# BeeLogic.net
KiCad netlist of a schematic drawn in EAGLE
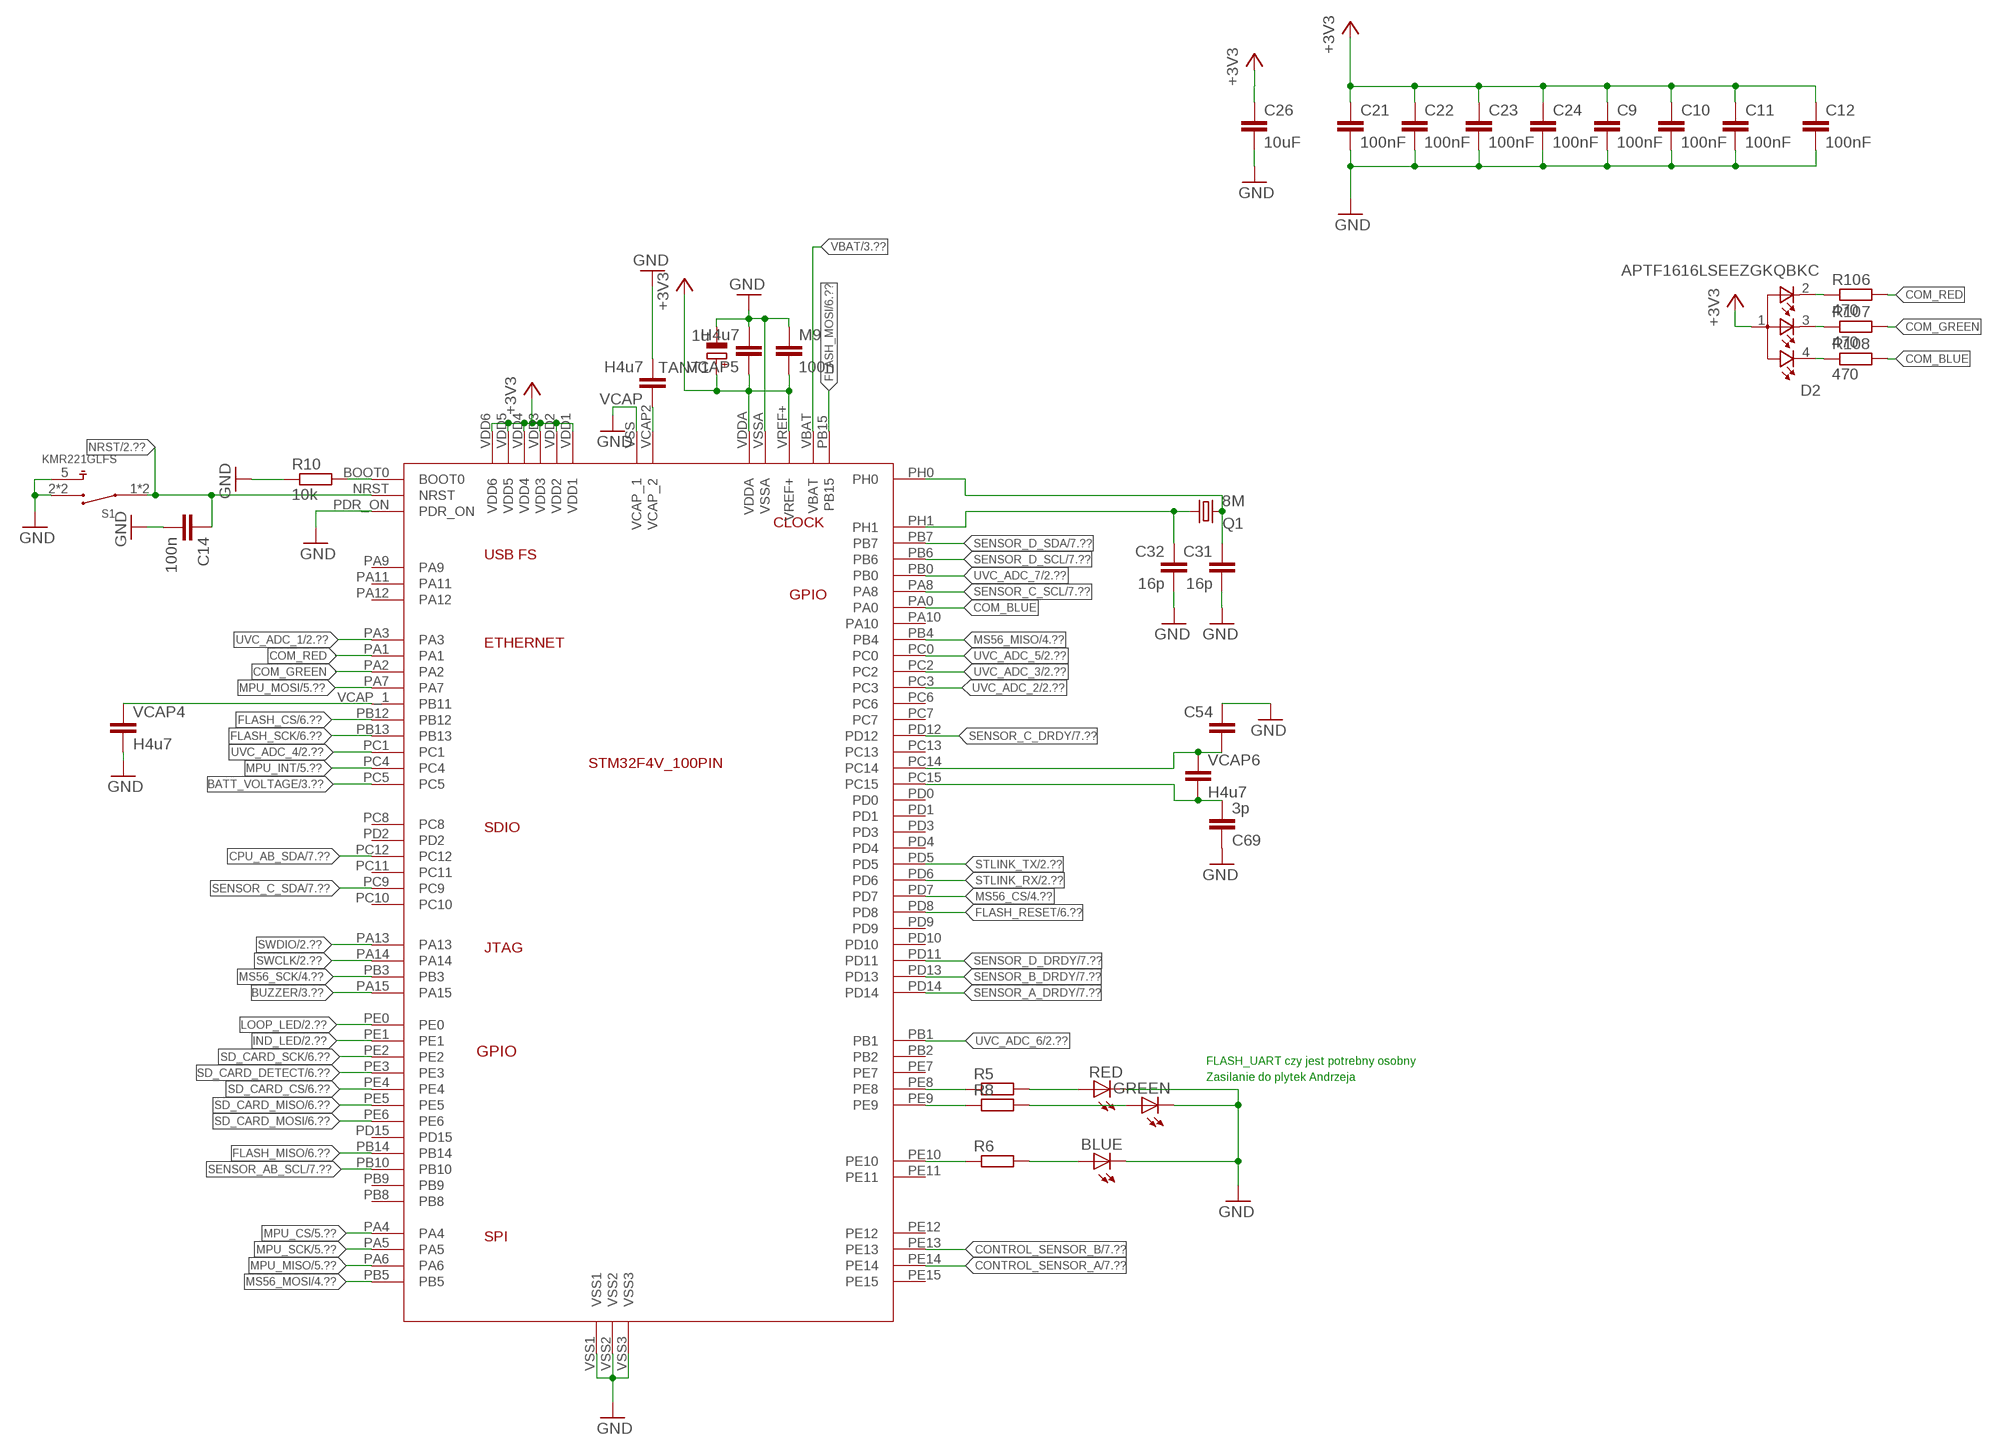
[diagram p0: schematic, sheet 1]
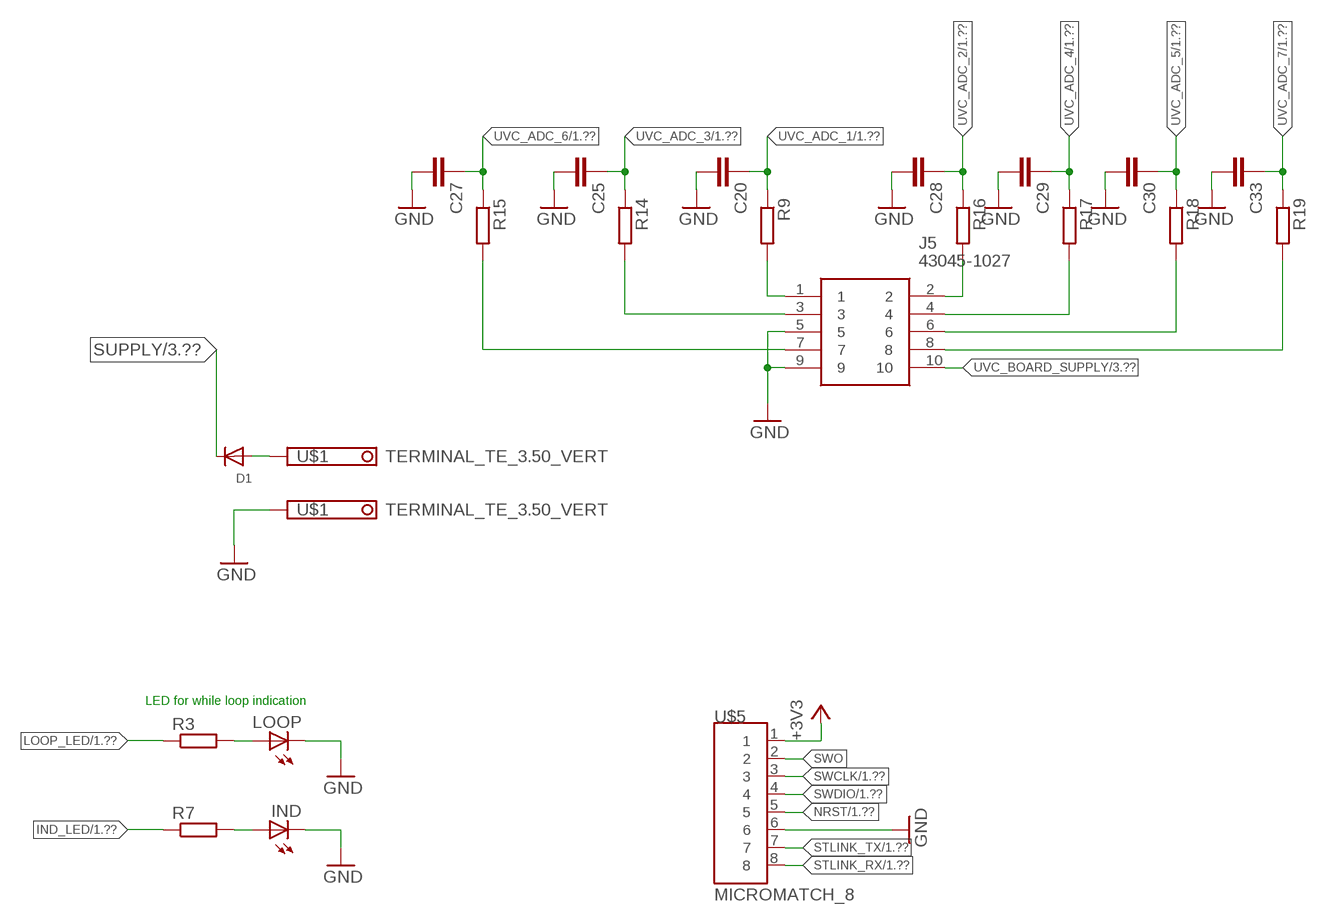
[diagram p1: schematic, sheet 2]
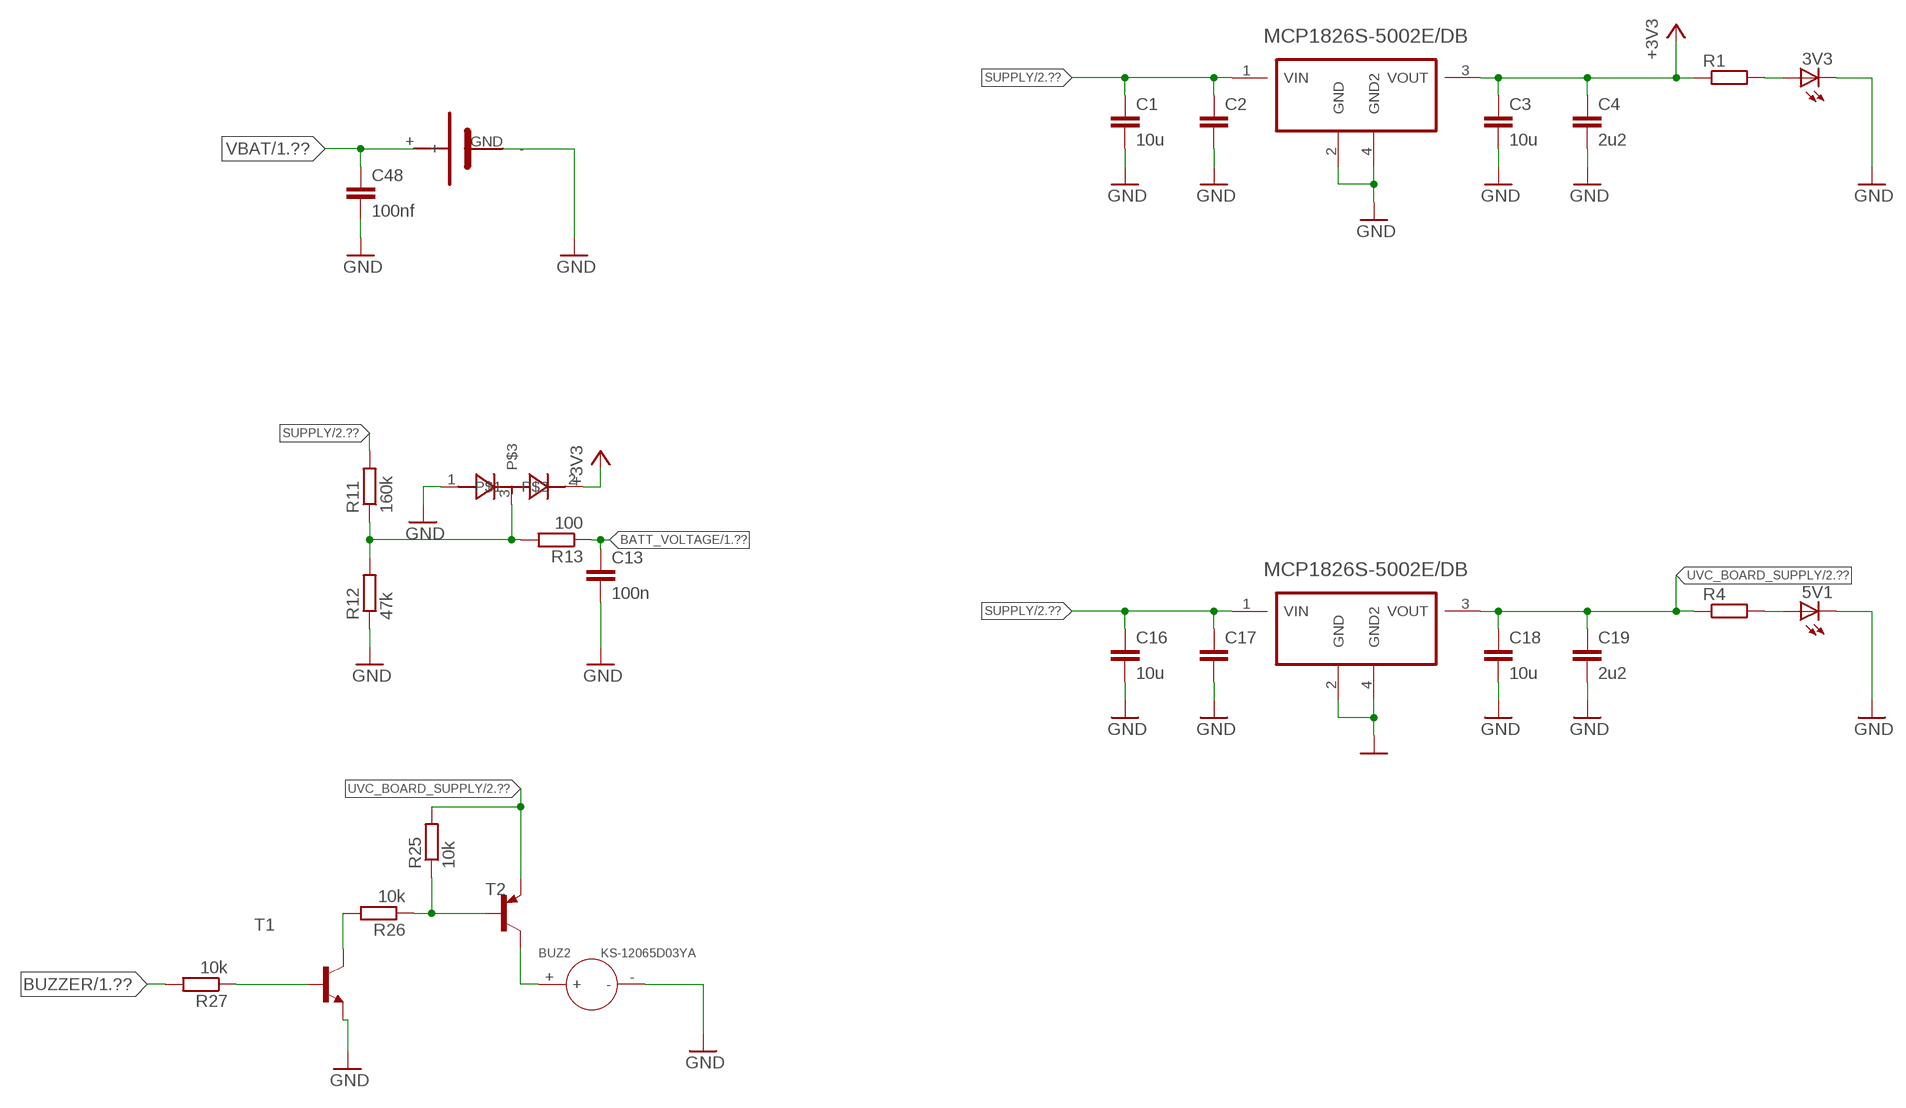
[diagram p2: schematic, sheet 3]
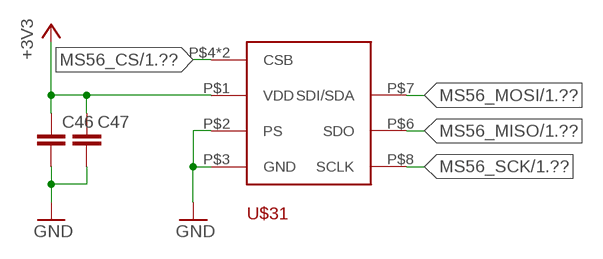
[diagram p3: schematic, sheet 4]
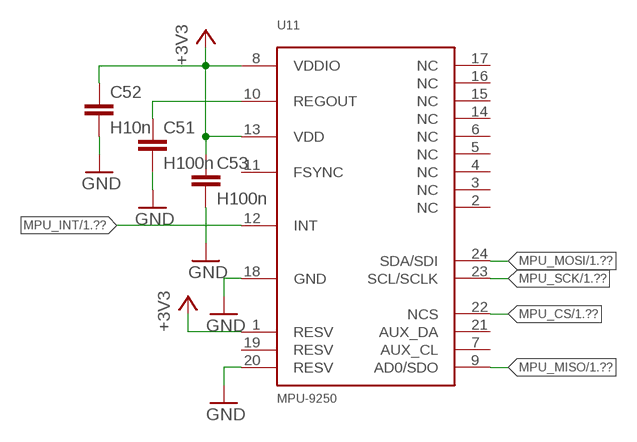
[diagram p4: schematic, sheet 5]
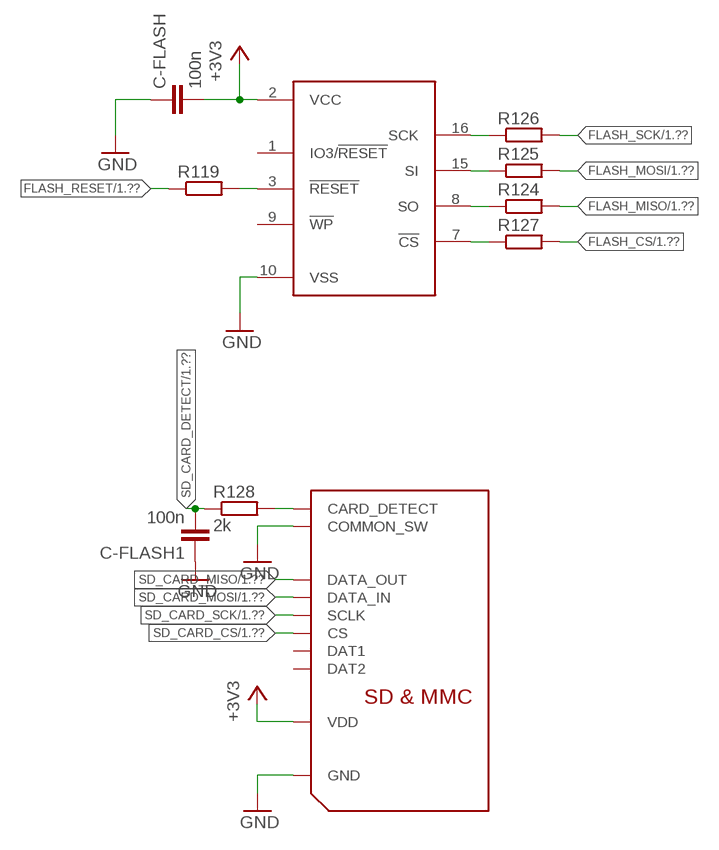
[diagram p5: schematic, sheet 6]
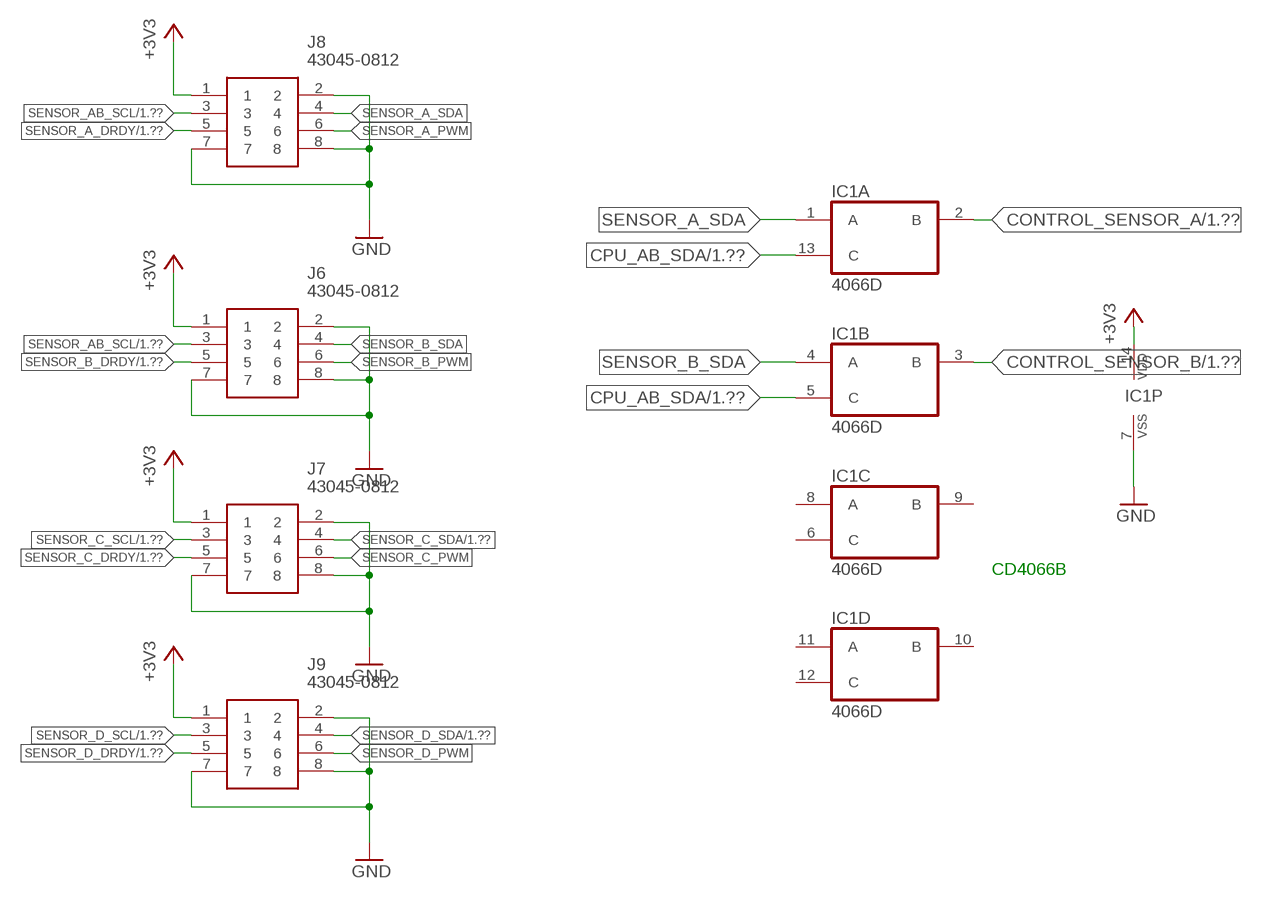
[diagram p6: schematic, sheet 7]

(export (version "E")
  (design (tool "Eeschema 10.0.6"))
  (components
    (comp (ref "IC1")
      (value "4066D")
      (footprint "eagle-import:SO14")
      (libsource (lib "eagle-import") (part "4066D"))
    )
    (comp (ref "J6")
      (value "43045-0812")
      (footprint "eagle-import:430450812")
      (fields (field (name "MOUSER_PART_NUMBER") "538-43045-0812"))
      (libsource (lib "eagle-import") (part "43045-0812"))
    )
    (comp (ref "J7")
      (value "43045-0812")
      (footprint "eagle-import:430450812")
      (fields (field (name "MOUSER_PART_NUMBER") "538-43045-0812"))
      (libsource (lib "eagle-import") (part "43045-0812"))
    )
    (comp (ref "J8")
      (value "43045-0812")
      (footprint "eagle-import:430450812")
      (fields (field (name "MOUSER_PART_NUMBER") "538-43045-0812"))
      (libsource (lib "eagle-import") (part "43045-0812"))
    )
    (comp (ref "J9")
      (value "43045-0812")
      (footprint "eagle-import:430450812")
      (fields (field (name "MOUSER_PART_NUMBER") "538-43045-0812"))
      (libsource (lib "eagle-import") (part "43045-0812"))
    )
    (comp (ref "BLUE")
      (value "LEDCHIPLED_0603")
      (footprint "eagle-import:CHIPLED_0603")
      (libsource (lib "eagle-import") (part "LEDCHIPLED_0603"))
    )
    (comp (ref "C9")
      (value "100nF")
      (footprint "eagle-import:C0603K")
      (libsource (lib "eagle-import") (part "rcl_334_C-EUC0603K"))
    )
    (comp (ref "C10")
      (value "100nF")
      (footprint "eagle-import:C0603K")
      (libsource (lib "eagle-import") (part "rcl_334_C-EUC0603K"))
    )
    (comp (ref "C11")
      (value "100nF")
      (footprint "eagle-import:C0603K")
      (libsource (lib "eagle-import") (part "rcl_334_C-EUC0603K"))
    )
    (comp (ref "C12")
      (value "100nF")
      (footprint "eagle-import:C0603K")
      (libsource (lib "eagle-import") (part "rcl_334_C-EUC0603K"))
    )
    (comp (ref "C14")
      (value "100n")
      (footprint "eagle-import:C0603K")
      (libsource (lib "eagle-import") (part "rcl_334_C-EUC0603K"))
    )
    (comp (ref "C21")
      (value "100nF")
      (footprint "eagle-import:C0603K")
      (libsource (lib "eagle-import") (part "rcl_334_C-EUC0603K"))
    )
    (comp (ref "C22")
      (value "100nF")
      (footprint "eagle-import:C0603K")
      (libsource (lib "eagle-import") (part "rcl_334_C-EUC0603K"))
    )
    (comp (ref "C23")
      (value "100nF")
      (footprint "eagle-import:C0603K")
      (libsource (lib "eagle-import") (part "rcl_334_C-EUC0603K"))
    )
    (comp (ref "C24")
      (value "100nF")
      (footprint "eagle-import:C0603K")
      (libsource (lib "eagle-import") (part "rcl_334_C-EUC0603K"))
    )
    (comp (ref "C26")
      (value "10uF")
      (footprint "eagle-import:C0805K")
      (libsource (lib "eagle-import") (part "rcl_334_C-EUC0805K"))
    )
    (comp (ref "C31")
      (value "16p")
      (footprint "eagle-import:C0603K")
      (libsource (lib "eagle-import") (part "rcl_334_C-EUC0603K"))
    )
    (comp (ref "C32")
      (value "16p")
      (footprint "eagle-import:C0603K")
      (libsource (lib "eagle-import") (part "rcl_334_C-EUC0603K"))
    )
    (comp (ref "C54")
      (value "3p")
      (footprint "eagle-import:C0603K")
      (libsource (lib "eagle-import") (part "rcl_334_C-EUC0603K"))
    )
    (comp (ref "C69")
      (value "3p")
      (footprint "eagle-import:C0603K")
      (libsource (lib "eagle-import") (part "rcl_334_C-EUC0603K"))
    )
    (comp (ref "D2")
      (value "APTF1616LSEEZGKQBKC")
      (footprint "eagle-import:LEDSC160X160X070-4N")
      (fields (field (name "MF") "Kingbright"))
      (libsource (lib "eagle-import") (part "APTF1616LSEEZGKQBKC"))
    )
    (comp (ref "GREEN")
      (value "LEDCHIPLED_0603")
      (footprint "eagle-import:CHIPLED_0603")
      (libsource (lib "eagle-import") (part "LEDCHIPLED_0603"))
    )
    (comp (ref "M9")
      (value "100n")
      (footprint "eagle-import:C0603K")
      (libsource (lib "eagle-import") (part "rcl_334_C-EUC0603K"))
    )
    (comp (ref "Q1")
      (value "8M")
      (footprint "eagle-import:CTS406")
      (libsource (lib "eagle-import") (part "CRYSTALCTS406"))
    )
    (comp (ref "R5")
      (value "R-EU_R0603")
      (footprint "eagle-import:R0603")
      (libsource (lib "eagle-import") (part "R-EU_R0603"))
    )
    (comp (ref "R6")
      (value "R-EU_R0603")
      (footprint "eagle-import:R0603")
      (libsource (lib "eagle-import") (part "R-EU_R0603"))
    )
    (comp (ref "R8")
      (value "R-EU_R0603")
      (footprint "eagle-import:R0603")
      (libsource (lib "eagle-import") (part "R-EU_R0603"))
    )
    (comp (ref "R10")
      (value "10k")
      (footprint "eagle-import:R0603")
      (libsource (lib "eagle-import") (part "R-EU_R0603"))
    )
    (comp (ref "R106")
      (value "470")
      (footprint "eagle-import:R0603")
      (libsource (lib "eagle-import") (part "R-EU_R0603"))
    )
    (comp (ref "R107")
      (value "470")
      (footprint "eagle-import:R0603")
      (libsource (lib "eagle-import") (part "R-EU_R0603"))
    )
    (comp (ref "R108")
      (value "470")
      (footprint "eagle-import:R0603")
      (libsource (lib "eagle-import") (part "R-EU_R0603"))
    )
    (comp (ref "RED")
      (value "LEDCHIPLED_0603")
      (footprint "eagle-import:CHIPLED_0603")
      (libsource (lib "eagle-import") (part "LEDCHIPLED_0603"))
    )
    (comp (ref "S1")
      (value "KMR221GLFS")
      (footprint "eagle-import:SW_KMR221GLFS")
      (fields (field (name "MF") "C&K Components"))
      (libsource (lib "eagle-import") (part "KMR221GLFS"))
    )
    (comp (ref "STM32F446VET1")
      (value "STM32F4V_100PIN_GPSBOARD")
      (footprint "eagle-import:LQFP100")
      (libsource (lib "eagle-import") (part "STM32F4V_100PIN_GPSBOARD"))
    )
    (comp (ref "TANT1")
      (value "1u")
      (footprint "eagle-import:SMC_A")
      (libsource (lib "eagle-import") (part "CPOL-EUSMCA"))
    )
    (comp (ref "VCAP")
      (value "H4u7")
      (footprint "eagle-import:C0805K")
      (libsource (lib "eagle-import") (part "rcl_334_C-EUC0805K"))
    )
    (comp (ref "VCAP4")
      (value "H4u7")
      (footprint "eagle-import:C0805K")
      (libsource (lib "eagle-import") (part "rcl_334_C-EUC0805K"))
    )
    (comp (ref "VCAP5")
      (value "H4u7")
      (footprint "eagle-import:C0805K")
      (libsource (lib "eagle-import") (part "rcl_334_C-EUC0805K"))
    )
    (comp (ref "VCAP6")
      (value "H4u7")
      (footprint "eagle-import:C0805K")
      (libsource (lib "eagle-import") (part "rcl_334_C-EUC0805K"))
    )
    (comp (ref "C46")
      (value "C-EUC0603")
      (footprint "eagle-import:C0603")
      (libsource (lib "eagle-import") (part "rcl_334_C-EUC0603"))
    )
    (comp (ref "C47")
      (value "C-EUC0603")
      (footprint "eagle-import:C0603")
      (libsource (lib "eagle-import") (part "rcl_334_C-EUC0603"))
    )
    (comp (ref "U$31")
      (value "MS56XX")
      (footprint "eagle-import:MS56XX")
      (libsource (lib "eagle-import") (part "MS56XX"))
    )
    (comp (ref "C-FLASH")
      (value "100n")
      (footprint "eagle-import:C0603K")
      (libsource (lib "eagle-import") (part "rcl_334_C-EUC0603K"))
    )
    (comp (ref "C-FLASH1")
      (value "100n")
      (footprint "eagle-import:C0603K")
      (libsource (lib "eagle-import") (part "rcl_334_C-EUC0603K"))
    )
    (comp (ref "R119")
      (value "R-EU_R0603")
      (footprint "eagle-import:R0603")
      (libsource (lib "eagle-import") (part "R-EU_R0603"))
    )
    (comp (ref "R124")
      (value "R-EU_R0603")
      (footprint "eagle-import:R0603")
      (libsource (lib "eagle-import") (part "R-EU_R0603"))
    )
    (comp (ref "R125")
      (value "R-EU_R0603")
      (footprint "eagle-import:R0603")
      (libsource (lib "eagle-import") (part "R-EU_R0603"))
    )
    (comp (ref "R126")
      (value "R-EU_R0603")
      (footprint "eagle-import:R0603")
      (libsource (lib "eagle-import") (part "R-EU_R0603"))
    )
    (comp (ref "R127")
      (value "R-EU_R0603")
      (footprint "eagle-import:R0603")
      (libsource (lib "eagle-import") (part "R-EU_R0603"))
    )
    (comp (ref "R128")
      (value "2k")
      (footprint "eagle-import:R0603")
      (libsource (lib "eagle-import") (part "R-EU_R0603"))
    )
    (comp (ref "U$2")
      (value "S25FLX")
      (footprint "eagle-import:SOIC16")
      (libsource (lib "eagle-import") (part "S25FLX"))
    )
    (comp (ref "U$4")
      (value "MOLEX_MICRO_SD_503182-1853")
      (footprint "eagle-import:MOLEX_MICRO_SD_503182-1853")
      (fields (field (name "SPICEPREFIX") "X"))
      (libsource (lib "eagle-import") (part "MOLEX_MICRO_SD_503182-1853"))
    )
    (comp (ref "3V3")
      (value "LEDCHIPLED_0603")
      (footprint "eagle-import:CHIPLED_0603")
      (libsource (lib "eagle-import") (part "LEDCHIPLED_0603"))
    )
    (comp (ref "5V1")
      (value "LEDCHIPLED_0603")
      (footprint "eagle-import:CHIPLED_0603")
      (libsource (lib "eagle-import") (part "LEDCHIPLED_0603"))
    )
    (comp (ref "BUZ2")
      (value "KS-12065D03YA")
      (footprint "eagle-import:BZ2-7.6-D12.0XH6.5MM")
      (libsource (lib "eagle-import") (part "DIP-BUZZER-3V(KS-12065D03YA)"))
    )
    (comp (ref "C1")
      (value "10u")
      (footprint "eagle-import:C0805K")
      (libsource (lib "eagle-import") (part "rcl_334_C-EUC0805K"))
    )
    (comp (ref "C2")
      (value "C-EUC0805K")
      (footprint "eagle-import:C0805K")
      (libsource (lib "eagle-import") (part "rcl_334_C-EUC0805K"))
    )
    (comp (ref "C3")
      (value "10u")
      (footprint "eagle-import:C0805K")
      (libsource (lib "eagle-import") (part "rcl_334_C-EUC0805K"))
    )
    (comp (ref "C4")
      (value "2u2")
      (footprint "eagle-import:C0805K")
      (libsource (lib "eagle-import") (part "rcl_334_C-EUC0805K"))
    )
    (comp (ref "C13")
      (value "100n")
      (footprint "eagle-import:C0603")
      (libsource (lib "eagle-import") (part "C-EUC0603"))
    )
    (comp (ref "C16")
      (value "10u")
      (footprint "eagle-import:C0805K")
      (libsource (lib "eagle-import") (part "rcl_334_C-EUC0805K"))
    )
    (comp (ref "C17")
      (value "C-EUC0805K")
      (footprint "eagle-import:C0805K")
      (libsource (lib "eagle-import") (part "rcl_334_C-EUC0805K"))
    )
    (comp (ref "C18")
      (value "10u")
      (footprint "eagle-import:C0805K")
      (libsource (lib "eagle-import") (part "rcl_334_C-EUC0805K"))
    )
    (comp (ref "C19")
      (value "2u2")
      (footprint "eagle-import:C0805K")
      (libsource (lib "eagle-import") (part "rcl_334_C-EUC0805K"))
    )
    (comp (ref "C48")
      (value "100nf")
      (footprint "eagle-import:C0805K")
      (libsource (lib "eagle-import") (part "rcl_334_C-EUC0805K"))
    )
    (comp (ref "R1")
      (value "R-EU_R0603")
      (footprint "eagle-import:R0603")
      (libsource (lib "eagle-import") (part "R-EU_R0603"))
    )
    (comp (ref "R4")
      (value "R-EU_R0603")
      (footprint "eagle-import:R0603")
      (libsource (lib "eagle-import") (part "R-EU_R0603"))
    )
    (comp (ref "R11")
      (value "160k")
      (footprint "eagle-import:R0603")
      (libsource (lib "eagle-import") (part "R-EU_R0603"))
    )
    (comp (ref "R12")
      (value "47k")
      (footprint "eagle-import:R0603")
      (libsource (lib "eagle-import") (part "R-EU_R0603"))
    )
    (comp (ref "R13")
      (value "100")
      (footprint "eagle-import:R0603")
      (libsource (lib "eagle-import") (part "R-EU_R0603"))
    )
    (comp (ref "R25")
      (value "10k")
      (footprint "eagle-import:R0603")
      (libsource (lib "eagle-import") (part "R-EU_R0603"))
    )
    (comp (ref "R26")
      (value "10k")
      (footprint "eagle-import:R0603")
      (libsource (lib "eagle-import") (part "R-EU_R0603"))
    )
    (comp (ref "R27")
      (value "10k")
      (footprint "eagle-import:R0603")
      (libsource (lib "eagle-import") (part "R-EU_R0603"))
    )
    (comp (ref "T1")
      (value "BCW81-NPN-SOT23-BEC")
      (footprint "eagle-import:SOT23-BEC")
      (libsource (lib "eagle-import") (part "-NPN-SOT23-BECBCW81"))
    )
    (comp (ref "T2")
      (value "BC807-16-PNP-SOT23-BEC")
      (footprint "eagle-import:SOT23-BEC")
      (libsource (lib "eagle-import") (part "-PNP-SOT23-BECBC807-16"))
    )
    (comp (ref "U$16")
      (value "BAS40W-04")
      (footprint "eagle-import:SOT65P210X110-3N")
      (libsource (lib "eagle-import") (part "BAS40W-04"))
    )
    (comp (ref "U$32")
      (value "CR1220_POZ")
      (footprint "eagle-import:CR1220_POZ")
      (libsource (lib "eagle-import") (part "CR1220_POZ"))
    )
    (comp (ref "U1")
      (value "MCP1826S-5002E/DB")
      (footprint "eagle-import:SOT230P700X180-4N")
      (fields (field (name "MF") "Microchip"))
      (libsource (lib "eagle-import") (part "MCP1826S-5002E/DB"))
    )
    (comp (ref "U3")
      (value "MCP1826S-5002E/DB")
      (footprint "eagle-import:SOT230P700X180-4N")
      (fields (field (name "MF") "Microchip"))
      (libsource (lib "eagle-import") (part "MCP1826S-5002E/DB"))
    )
    (comp (ref "C20")
      (value "C-EUC0603")
      (footprint "eagle-import:C0603")
      (libsource (lib "eagle-import") (part "resistor_348_C-EUC0603"))
    )
    (comp (ref "C25")
      (value "C-EUC0603")
      (footprint "eagle-import:C0603")
      (libsource (lib "eagle-import") (part "resistor_348_C-EUC0603"))
    )
    (comp (ref "C27")
      (value "C-EUC0603")
      (footprint "eagle-import:C0603")
      (libsource (lib "eagle-import") (part "resistor_348_C-EUC0603"))
    )
    (comp (ref "C28")
      (value "C-EUC0603")
      (footprint "eagle-import:C0603")
      (libsource (lib "eagle-import") (part "resistor_348_C-EUC0603"))
    )
    (comp (ref "C29")
      (value "C-EUC0603")
      (footprint "eagle-import:C0603")
      (libsource (lib "eagle-import") (part "resistor_348_C-EUC0603"))
    )
    (comp (ref "C30")
      (value "C-EUC0603")
      (footprint "eagle-import:C0603")
      (libsource (lib "eagle-import") (part "resistor_348_C-EUC0603"))
    )
    (comp (ref "C33")
      (value "C-EUC0603")
      (footprint "eagle-import:C0603")
      (libsource (lib "eagle-import") (part "resistor_348_C-EUC0603"))
    )
    (comp (ref "D1")
      (value "DIODE_SOD-123FL")
      (footprint "eagle-import:SOD-123FL")
      (libsource (lib "eagle-import") (part "DIODE_SOD-123FL"))
    )
    (comp (ref "IND")
      (value "LEDCHIPLED_0603")
      (footprint "eagle-import:CHIPLED_0603")
      (libsource (lib "eagle-import") (part "LEDCHIPLED_0603"))
    )
    (comp (ref "J5")
      (value "43045-1027")
      (footprint "eagle-import:43045-1028_1")
      (fields (field (name "MOUSER_PART_NUMBER") "538-43045-1027") (field (name "RS_PART_NUMBER") "6700469P"))
      (libsource (lib "eagle-import") (part "43045-1027"))
    )
    (comp (ref "LOOP")
      (value "LEDCHIPLED_0603")
      (footprint "eagle-import:CHIPLED_0603")
      (libsource (lib "eagle-import") (part "LEDCHIPLED_0603"))
    )
    (comp (ref "R3")
      (value "R-EU_R0603")
      (footprint "eagle-import:R0603")
      (libsource (lib "eagle-import") (part "R-EU_R0603"))
    )
    (comp (ref "R7")
      (value "R-EU_R0603")
      (footprint "eagle-import:R0603")
      (libsource (lib "eagle-import") (part "R-EU_R0603"))
    )
    (comp (ref "R9")
      (value "R-EU_R0603")
      (footprint "eagle-import:R0603")
      (libsource (lib "eagle-import") (part "resistor_348_R-EU_R0603"))
    )
    (comp (ref "R14")
      (value "R-EU_R0603")
      (footprint "eagle-import:R0603")
      (libsource (lib "eagle-import") (part "resistor_348_R-EU_R0603"))
    )
    (comp (ref "R15")
      (value "R-EU_R0603")
      (footprint "eagle-import:R0603")
      (libsource (lib "eagle-import") (part "resistor_348_R-EU_R0603"))
    )
    (comp (ref "R16")
      (value "R-EU_R0603")
      (footprint "eagle-import:R0603")
      (libsource (lib "eagle-import") (part "resistor_348_R-EU_R0603"))
    )
    (comp (ref "R17")
      (value "R-EU_R0603")
      (footprint "eagle-import:R0603")
      (libsource (lib "eagle-import") (part "resistor_348_R-EU_R0603"))
    )
    (comp (ref "R18")
      (value "R-EU_R0603")
      (footprint "eagle-import:R0603")
      (libsource (lib "eagle-import") (part "resistor_348_R-EU_R0603"))
    )
    (comp (ref "R19")
      (value "R-EU_R0603")
      (footprint "eagle-import:R0603")
      (libsource (lib "eagle-import") (part "resistor_348_R-EU_R0603"))
    )
    (comp (ref "U$1")
      (value "TERMINAL_TE_3.50_VERT")
      (footprint "eagle-import:TE_3.5_TERMINAL_VERT")
      (libsource (lib "eagle-import") (part "TERMINAL_TE_3.50_VERT"))
    )
    (comp (ref "U$5")
      (value "MICROMATCH_8")
      (footprint "eagle-import:MICROMATCH_8")
      (libsource (lib "eagle-import") (part "MICROMATCH_8"))
    )
    (comp (ref "C51")
      (value "H100n")
      (footprint "eagle-import:C0603K")
      (libsource (lib "eagle-import") (part "rcl_334_C-EUC0603K"))
    )
    (comp (ref "C52")
      (value "H10n")
      (footprint "eagle-import:C0603K")
      (libsource (lib "eagle-import") (part "rcl_334_C-EUC0603K"))
    )
    (comp (ref "C53")
      (value "H100n")
      (footprint "eagle-import:C0603K")
      (libsource (lib "eagle-import") (part "rcl_334_C-EUC0603K"))
    )
    (comp (ref "U11")
      (value "MPU-9250")
      (footprint "eagle-import:MPU-9250")
      (fields (field (name "MF") "InvenSense"))
      (libsource (lib "eagle-import") (part "MPU-9250"))
    )
  )
  (nets
    (net (code "1") (name "+3V3") (class "Default")
      (node (ref "C-FLASH") (pin "2") (pinfunction "2_2") (pintype "passive"))
      (node (ref "C10") (pin "1") (pinfunction "1_1") (pintype "passive"))
      (node (ref "C11") (pin "1") (pinfunction "1_1") (pintype "passive"))
      (node (ref "C12") (pin "1") (pinfunction "1_1") (pintype "passive"))
      (node (ref "C21") (pin "1") (pinfunction "1_1") (pintype "passive"))
      (node (ref "C22") (pin "1") (pinfunction "1_1") (pintype "passive"))
      (node (ref "C23") (pin "1") (pinfunction "1_1") (pintype "passive"))
      (node (ref "C24") (pin "1") (pinfunction "1_1") (pintype "passive"))
      (node (ref "C26") (pin "1") (pinfunction "1_1") (pintype "passive"))
      (node (ref "C3") (pin "1") (pinfunction "1_1") (pintype "passive"))
      (node (ref "C4") (pin "1") (pinfunction "1_1") (pintype "passive"))
      (node (ref "C46") (pin "1") (pinfunction "1_1") (pintype "passive"))
      (node (ref "C47") (pin "1") (pinfunction "1_1") (pintype "passive"))
      (node (ref "C52") (pin "1") (pinfunction "1_1") (pintype "passive"))
      (node (ref "C53") (pin "1") (pinfunction "1_1") (pintype "passive"))
      (node (ref "C9") (pin "1") (pinfunction "1_1") (pintype "passive"))
      (node (ref "D2") (pin "1") (pinfunction "1_1") (pintype "passive"))
      (node (ref "IC1") (pin "14") (pinfunction "VDD_14") (pintype "power_in"))
      (node (ref "J6") (pin "1") (pinfunction "1_1") (pintype "bidirectional"))
      (node (ref "J7") (pin "1") (pinfunction "1_1") (pintype "bidirectional"))
      (node (ref "J8") (pin "1") (pinfunction "1_1") (pintype "bidirectional"))
      (node (ref "J9") (pin "1") (pinfunction "1_1") (pintype "bidirectional"))
      (node (ref "M9") (pin "2") (pinfunction "2_2") (pintype "passive"))
      (node (ref "R1") (pin "1") (pinfunction "1_1") (pintype "passive"))
      (node (ref "STM32F446VET1") (pin "VDD1") (pinfunction "VDD1_VDD1") (pintype "power_in"))
      (node (ref "STM32F446VET1") (pin "VDD2") (pinfunction "VDD2_VDD2") (pintype "power_in"))
      (node (ref "STM32F446VET1") (pin "VDD3") (pinfunction "VDD3_VDD3") (pintype "power_in"))
      (node (ref "STM32F446VET1") (pin "VDD4") (pinfunction "VDD4_VDD4") (pintype "power_in"))
      (node (ref "STM32F446VET1") (pin "VDD5") (pinfunction "VDD5_VDD5") (pintype "power_in"))
      (node (ref "STM32F446VET1") (pin "VDD6") (pinfunction "VDD6_VDD6") (pintype "power_in"))
      (node (ref "STM32F446VET1") (pin "VDDA") (pinfunction "VDDA_VDDA") (pintype "bidirectional"))
      (node (ref "STM32F446VET1") (pin "VREF+") (pinfunction "VREF+_VREF+") (pintype "bidirectional"))
      (node (ref "TANT1") (pin "+") (pinfunction "+_+") (pintype "passive"))
      (node (ref "U$16") (pin "2") (pinfunction "P$2_2") (pintype "bidirectional"))
      (node (ref "U$2") (pin "2") (pinfunction "VCC_2") (pintype "bidirectional"))
      (node (ref "U$31") (pin "P$1") (pinfunction "VDD_P$1") (pintype "bidirectional"))
      (node (ref "U$4") (pin "PIN4") (pinfunction "VDD_PIN4") (pintype "power_in"))
      (node (ref "U$5") (pin "1") (pinfunction "1_1") (pintype "passive"))
      (node (ref "U1") (pin "3") (pinfunction "VOUT_3") (pintype "output"))
      (node (ref "U11") (pin "1") (pinfunction "RESV_1") (pintype "bidirectional"))
      (node (ref "U11") (pin "13") (pinfunction "VDD_13") (pintype "bidirectional"))
      (node (ref "U11") (pin "8") (pinfunction "VDDIO_8") (pintype "bidirectional"))
      (node (ref "VCAP5") (pin "1") (pinfunction "1_1") (pintype "passive"))
    )
    (net (code "2") (name "BATT_VOLTAGE") (class "Default")
      (node (ref "C13") (pin "1") (pinfunction "1_1") (pintype "passive"))
      (node (ref "R13") (pin "1") (pinfunction "1_1") (pintype "passive"))
      (node (ref "STM32F446VET1") (pin "PC5") (pinfunction "PC5_PC5") (pintype "bidirectional"))
    )
    (net (code "3") (name "BUZZER") (class "Default")
      (node (ref "R27") (pin "2") (pinfunction "2_2") (pintype "passive"))
      (node (ref "STM32F446VET1") (pin "PA15") (pinfunction "PA15_PA15") (pintype "bidirectional"))
    )
    (net (code "4") (name "COM_BLUE") (class "Default")
      (node (ref "R108") (pin "2") (pinfunction "2_2") (pintype "passive"))
      (node (ref "STM32F446VET1") (pin "PA0") (pinfunction "PA0_PA0") (pintype "bidirectional"))
    )
    (net (code "5") (name "COM_GREEN") (class "Default")
      (node (ref "R107") (pin "2") (pinfunction "2_2") (pintype "passive"))
      (node (ref "STM32F446VET1") (pin "PA2") (pinfunction "PA2_PA2") (pintype "bidirectional"))
    )
    (net (code "6") (name "COM_RED") (class "Default")
      (node (ref "R106") (pin "2") (pinfunction "2_2") (pintype "passive"))
      (node (ref "STM32F446VET1") (pin "PA1") (pinfunction "PA1_PA1") (pintype "bidirectional"))
    )
    (net (code "7") (name "CONTROL_SENSOR_A") (class "Default")
      (node (ref "IC1") (pin "2") (pinfunction "B_2") (pintype "tri_state"))
      (node (ref "STM32F446VET1") (pin "PE14") (pinfunction "PE14_PE14") (pintype "bidirectional"))
    )
    (net (code "8") (name "CONTROL_SENSOR_B") (class "Default")
      (node (ref "IC1") (pin "3") (pinfunction "B_3") (pintype "tri_state"))
      (node (ref "STM32F446VET1") (pin "PE13") (pinfunction "PE13_PE13") (pintype "bidirectional"))
    )
    (net (code "9") (name "CPU_AB_SDA") (class "Default")
      (node (ref "IC1") (pin "13") (pinfunction "C_13") (pintype "input"))
      (node (ref "IC1") (pin "5") (pinfunction "C_5") (pintype "input"))
      (node (ref "STM32F446VET1") (pin "PC12") (pinfunction "PC12_PC12") (pintype "bidirectional"))
    )
    (net (code "10") (name "FLASH_CS") (class "Default")
      (node (ref "R127") (pin "2") (pinfunction "2_2") (pintype "passive"))
      (node (ref "STM32F446VET1") (pin "PB12") (pinfunction "PB12_PB12") (pintype "bidirectional"))
    )
    (net (code "11") (name "FLASH_MISO") (class "Default")
      (node (ref "R124") (pin "2") (pinfunction "2_2") (pintype "passive"))
      (node (ref "STM32F446VET1") (pin "PB14") (pinfunction "PB14_PB14") (pintype "bidirectional"))
    )
    (net (code "12") (name "FLASH_MOSI") (class "Default")
      (node (ref "R125") (pin "2") (pinfunction "2_2") (pintype "passive"))
      (node (ref "STM32F446VET1") (pin "PB15") (pinfunction "PB15_PB15") (pintype "bidirectional"))
    )
    (net (code "13") (name "FLASH_RESET") (class "Default")
      (node (ref "R119") (pin "1") (pinfunction "1_1") (pintype "passive"))
      (node (ref "STM32F446VET1") (pin "PD8") (pinfunction "PD8_PD8") (pintype "bidirectional"))
    )
    (net (code "14") (name "FLASH_SCK") (class "Default")
      (node (ref "R126") (pin "2") (pinfunction "2_2") (pintype "passive"))
      (node (ref "STM32F446VET1") (pin "PB13") (pinfunction "PB13_PB13") (pintype "bidirectional"))
    )
    (net (code "15") (name "GND") (class "Default")
      (node (ref "3V3") (pin "C") (pinfunction "C_C") (pintype "passive"))
      (node (ref "5V1") (pin "C") (pinfunction "C_C") (pintype "passive"))
      (node (ref "BLUE") (pin "C") (pinfunction "C_C") (pintype "passive"))
      (node (ref "BUZ2") (pin "-") (pinfunction "-_-") (pintype "bidirectional"))
      (node (ref "C-FLASH") (pin "1") (pinfunction "1_1") (pintype "passive"))
      (node (ref "C-FLASH1") (pin "1") (pinfunction "1_1") (pintype "passive"))
      (node (ref "C1") (pin "2") (pinfunction "2_2") (pintype "passive"))
      (node (ref "C10") (pin "2") (pinfunction "2_2") (pintype "passive"))
      (node (ref "C11") (pin "2") (pinfunction "2_2") (pintype "passive"))
      (node (ref "C12") (pin "2") (pinfunction "2_2") (pintype "passive"))
      (node (ref "C13") (pin "2") (pinfunction "2_2") (pintype "passive"))
      (node (ref "C14") (pin "2") (pinfunction "2_2") (pintype "passive"))
      (node (ref "C16") (pin "2") (pinfunction "2_2") (pintype "passive"))
      (node (ref "C17") (pin "2") (pinfunction "2_2") (pintype "passive"))
      (node (ref "C18") (pin "2") (pinfunction "2_2") (pintype "passive"))
      (node (ref "C19") (pin "2") (pinfunction "2_2") (pintype "passive"))
      (node (ref "C2") (pin "2") (pinfunction "2_2") (pintype "passive"))
      (node (ref "C20") (pin "2") (pinfunction "2_2") (pintype "passive"))
      (node (ref "C21") (pin "2") (pinfunction "2_2") (pintype "passive"))
      (node (ref "C22") (pin "2") (pinfunction "2_2") (pintype "passive"))
      (node (ref "C23") (pin "2") (pinfunction "2_2") (pintype "passive"))
      (node (ref "C24") (pin "2") (pinfunction "2_2") (pintype "passive"))
      (node (ref "C25") (pin "2") (pinfunction "2_2") (pintype "passive"))
      (node (ref "C26") (pin "2") (pinfunction "2_2") (pintype "passive"))
      (node (ref "C27") (pin "2") (pinfunction "2_2") (pintype "passive"))
      (node (ref "C28") (pin "2") (pinfunction "2_2") (pintype "passive"))
      (node (ref "C29") (pin "2") (pinfunction "2_2") (pintype "passive"))
      (node (ref "C3") (pin "2") (pinfunction "2_2") (pintype "passive"))
      (node (ref "C30") (pin "2") (pinfunction "2_2") (pintype "passive"))
      (node (ref "C31") (pin "2") (pinfunction "2_2") (pintype "passive"))
      (node (ref "C32") (pin "2") (pinfunction "2_2") (pintype "passive"))
      (node (ref "C33") (pin "2") (pinfunction "2_2") (pintype "passive"))
      (node (ref "C4") (pin "2") (pinfunction "2_2") (pintype "passive"))
      (node (ref "C46") (pin "2") (pinfunction "2_2") (pintype "passive"))
      (node (ref "C47") (pin "2") (pinfunction "2_2") (pintype "passive"))
      (node (ref "C48") (pin "2") (pinfunction "2_2") (pintype "passive"))
      (node (ref "C51") (pin "2") (pinfunction "2_2") (pintype "passive"))
      (node (ref "C52") (pin "2") (pinfunction "2_2") (pintype "passive"))
      (node (ref "C53") (pin "2") (pinfunction "2_2") (pintype "passive"))
      (node (ref "C54") (pin "2") (pinfunction "2_2") (pintype "passive"))
      (node (ref "C69") (pin "1") (pinfunction "1_1") (pintype "passive"))
      (node (ref "C9") (pin "2") (pinfunction "2_2") (pintype "passive"))
      (node (ref "GREEN") (pin "C") (pinfunction "C_C") (pintype "passive"))
      (node (ref "IC1") (pin "7") (pinfunction "VSS_7") (pintype "power_in"))
      (node (ref "IND") (pin "C") (pinfunction "C_C") (pintype "passive"))
      (node (ref "J5") (pin "5") (pinfunction "5_5") (pintype "bidirectional"))
      (node (ref "J5") (pin "9") (pinfunction "9_9") (pintype "bidirectional"))
      (node (ref "J6") (pin "2") (pinfunction "2_2") (pintype "bidirectional"))
      (node (ref "J6") (pin "7") (pinfunction "7_7") (pintype "bidirectional"))
      (node (ref "J6") (pin "8") (pinfunction "8_8") (pintype "bidirectional"))
      (node (ref "J7") (pin "2") (pinfunction "2_2") (pintype "bidirectional"))
      (node (ref "J7") (pin "7") (pinfunction "7_7") (pintype "bidirectional"))
      (node (ref "J7") (pin "8") (pinfunction "8_8") (pintype "bidirectional"))
      (node (ref "J8") (pin "2") (pinfunction "2_2") (pintype "bidirectional"))
      (node (ref "J8") (pin "7") (pinfunction "7_7") (pintype "bidirectional"))
      (node (ref "J8") (pin "8") (pinfunction "8_8") (pintype "bidirectional"))
      (node (ref "J9") (pin "2") (pinfunction "2_2") (pintype "bidirectional"))
      (node (ref "J9") (pin "7") (pinfunction "7_7") (pintype "bidirectional"))
      (node (ref "J9") (pin "8") (pinfunction "8_8") (pintype "bidirectional"))
      (node (ref "LOOP") (pin "C") (pinfunction "C_C") (pintype "passive"))
      (node (ref "M9") (pin "1") (pinfunction "1_1") (pintype "passive"))
      (node (ref "R10") (pin "1") (pinfunction "1_1") (pintype "passive"))
      (node (ref "R12") (pin "1") (pinfunction "1_1") (pintype "passive"))
      (node (ref "RED") (pin "C") (pinfunction "C_C") (pintype "passive"))
      (node (ref "S1") (pin "2") (pinfunction "3_2") (pintype "passive"))
      (node (ref "S1") (pin "3") (pinfunction "3_3") (pintype "passive"))
      (node (ref "S1") (pin "5") (pinfunction "5_5") (pintype "passive"))
      (node (ref "STM32F446VET1") (pin "PDR_ON") (pinfunction "PDR_ON_PDR_ON") (pintype "bidirectional"))
      (node (ref "STM32F446VET1") (pin "VSS") (pinfunction "VCAP_1_VSS") (pintype "bidirectional"))
      (node (ref "STM32F446VET1") (pin "VSS1") (pinfunction "VSS1_VSS1") (pintype "power_in"))
      (node (ref "STM32F446VET1") (pin "VSS2") (pinfunction "VSS2_VSS2") (pintype "power_in"))
      (node (ref "STM32F446VET1") (pin "VSS3") (pinfunction "VSS3_VSS3") (pintype "power_in"))
      (node (ref "STM32F446VET1") (pin "VSSA") (pinfunction "VSSA_VSSA") (pintype "bidirectional"))
      (node (ref "T1") (pin "E") (pinfunction "E_E") (pintype "passive"))
      (node (ref "TANT1") (pin "-") (pinfunction "-_-") (pintype "passive"))
      (node (ref "U$1") (pin "P$2") (pinfunction "K1_P$2") (pintype "passive"))
      (node (ref "U$16") (pin "1") (pinfunction "P$1_1") (pintype "bidirectional"))
      (node (ref "U$2") (pin "10") (pinfunction "VSS_10") (pintype "bidirectional"))
      (node (ref "U$31") (pin "P$2") (pinfunction "PS_P$2") (pintype "bidirectional"))
      (node (ref "U$31") (pin "P$3") (pinfunction "GND_P$3") (pintype "bidirectional"))
      (node (ref "U$32") (pin "GND") (pinfunction "-_GND") (pintype "bidirectional"))
      (node (ref "U$4") (pin "DETECT_GND") (pinfunction "COMMON_SW_DETECT_GND") (pintype "passive"))
      (node (ref "U$4") (pin "PIN6") (pinfunction "GND_PIN6") (pintype "power_in"))
      (node (ref "U$5") (pin "6") (pinfunction "6_6") (pintype "passive"))
      (node (ref "U1") (pin "2") (pinfunction "GND_2") (pintype "passive"))
      (node (ref "U1") (pin "4") (pinfunction "GND2_4") (pintype "passive"))
      (node (ref "U11") (pin "18") (pinfunction "GND_18") (pintype "bidirectional"))
      (node (ref "U11") (pin "20") (pinfunction "RESV_20") (pintype "bidirectional"))
      (node (ref "U3") (pin "2") (pinfunction "GND_2") (pintype "passive"))
      (node (ref "U3") (pin "4") (pinfunction "GND2_4") (pintype "passive"))
      (node (ref "VCAP") (pin "2") (pinfunction "2_2") (pintype "passive"))
      (node (ref "VCAP4") (pin "2") (pinfunction "2_2") (pintype "passive"))
      (node (ref "VCAP5") (pin "2") (pinfunction "2_2") (pintype "passive"))
    )
    (net (code "16") (name "IND_LED") (class "Default")
      (node (ref "R7") (pin "1") (pinfunction "1_1") (pintype "passive"))
      (node (ref "STM32F446VET1") (pin "PE1") (pinfunction "PE1_PE1") (pintype "bidirectional"))
    )
    (net (code "17") (name "LOOP_LED") (class "Default")
      (node (ref "R3") (pin "1") (pinfunction "1_1") (pintype "passive"))
      (node (ref "STM32F446VET1") (pin "PE0") (pinfunction "PE0_PE0") (pintype "bidirectional"))
    )
    (net (code "18") (name "MPU_CS") (class "Default")
      (node (ref "STM32F446VET1") (pin "PA4") (pinfunction "PA4_PA4") (pintype "bidirectional"))
      (node (ref "U11") (pin "22") (pinfunction "NCS_22") (pintype "bidirectional"))
    )
    (net (code "19") (name "MPU_INT") (class "Default")
      (node (ref "STM32F446VET1") (pin "PC4") (pinfunction "PC4_PC4") (pintype "bidirectional"))
      (node (ref "U11") (pin "12") (pinfunction "INT_12") (pintype "bidirectional"))
    )
    (net (code "20") (name "MPU_MISO") (class "Default")
      (node (ref "STM32F446VET1") (pin "PA6") (pinfunction "PA6_PA6") (pintype "bidirectional"))
      (node (ref "U11") (pin "9") (pinfunction "AD0/SDO_9") (pintype "bidirectional"))
    )
    (net (code "21") (name "MPU_MOSI") (class "Default")
      (node (ref "STM32F446VET1") (pin "PA7") (pinfunction "PA7_PA7") (pintype "bidirectional"))
      (node (ref "U11") (pin "24") (pinfunction "SDA/SDI_24") (pintype "bidirectional"))
    )
    (net (code "22") (name "MPU_SCK") (class "Default")
      (node (ref "STM32F446VET1") (pin "PA5") (pinfunction "PA5_PA5") (pintype "bidirectional"))
      (node (ref "U11") (pin "23") (pinfunction "SCL/SCLK_23") (pintype "bidirectional"))
    )
    (net (code "23") (name "MS56_CS") (class "Default")
      (node (ref "STM32F446VET1") (pin "PD7") (pinfunction "PD7_PD7") (pintype "bidirectional"))
      (node (ref "U$31") (pin "P$4") (pinfunction "CSB_P$4") (pintype "bidirectional"))
      (node (ref "U$31") (pin "P$5") (pinfunction "CSB_P$5") (pintype "bidirectional"))
    )
    (net (code "24") (name "MS56_MISO") (class "Default")
      (node (ref "STM32F446VET1") (pin "PB4") (pinfunction "PB4_PB4") (pintype "bidirectional"))
      (node (ref "U$31") (pin "P$6") (pinfunction "SDO_P$6") (pintype "bidirectional"))
    )
    (net (code "25") (name "MS56_MOSI") (class "Default")
      (node (ref "STM32F446VET1") (pin "PB5") (pinfunction "PB5_PB5") (pintype "bidirectional"))
      (node (ref "U$31") (pin "P$7") (pinfunction "SDI/SDA_P$7") (pintype "bidirectional"))
    )
    (net (code "26") (name "MS56_SCK") (class "Default")
      (node (ref "STM32F446VET1") (pin "PB3") (pinfunction "PB3_PB3") (pintype "bidirectional"))
      (node (ref "U$31") (pin "P$8") (pinfunction "SCLK_P$8") (pintype "bidirectional"))
    )
    (net (code "27") (name "NRST") (class "Default")
      (node (ref "C14") (pin "1") (pinfunction "1_1") (pintype "passive"))
      (node (ref "S1") (pin "1") (pinfunction "1_1") (pintype "passive"))
      (node (ref "S1") (pin "4") (pinfunction "1_4") (pintype "passive"))
      (node (ref "STM32F446VET1") (pin "NRST") (pinfunction "NRST_NRST") (pintype "bidirectional"))
      (node (ref "U$5") (pin "5") (pinfunction "5_5") (pintype "passive"))
    )
    (net (code "28") (name "Net-(3V3-PadA)") (class "Default")
      (node (ref "3V3") (pin "A") (pinfunction "A_A") (pintype "passive"))
      (node (ref "R1") (pin "2") (pinfunction "2_2") (pintype "passive"))
    )
    (net (code "29") (name "Net-(5V1-PadA)") (class "Default")
      (node (ref "5V1") (pin "A") (pinfunction "A_A") (pintype "passive"))
      (node (ref "R4") (pin "2") (pinfunction "2_2") (pintype "passive"))
    )
    (net (code "30") (name "Net-(BLUE-PadA)") (class "Default")
      (node (ref "BLUE") (pin "A") (pinfunction "A_A") (pintype "passive"))
      (node (ref "R6") (pin "2") (pinfunction "2_2") (pintype "passive"))
    )
    (net (code "31") (name "Net-(BUZ2-Pad+)") (class "Default")
      (node (ref "BUZ2") (pin "+") (pinfunction "+_+") (pintype "bidirectional"))
      (node (ref "T2") (pin "C") (pinfunction "C_C") (pintype "passive"))
    )
    (net (code "32") (name "Net-(C32-Pad1)") (class "Default")
      (node (ref "C32") (pin "1") (pinfunction "1_1") (pintype "passive"))
      (node (ref "Q1") (pin "1") (pinfunction "1_1") (pintype "passive"))
      (node (ref "STM32F446VET1") (pin "PH1") (pinfunction "PH1_PH1") (pintype "bidirectional"))
    )
    (net (code "33") (name "Net-(C54-Pad1)") (class "Default")
      (node (ref "C54") (pin "1") (pinfunction "1_1") (pintype "passive"))
      (node (ref "STM32F446VET1") (pin "PC14") (pinfunction "PC14_PC14") (pintype "bidirectional"))
      (node (ref "VCAP6") (pin "1") (pinfunction "1_1") (pintype "passive"))
    )
    (net (code "34") (name "Net-(C69-Pad2)") (class "Default")
      (node (ref "C69") (pin "2") (pinfunction "2_2") (pintype "passive"))
      (node (ref "STM32F446VET1") (pin "PC15") (pinfunction "PC15_PC15") (pintype "bidirectional"))
      (node (ref "VCAP6") (pin "2") (pinfunction "2_2") (pintype "passive"))
    )
    (net (code "35") (name "Net-(D2-Pad2)") (class "Default")
      (node (ref "D2") (pin "2") (pinfunction "2_2") (pintype "passive"))
      (node (ref "R106") (pin "1") (pinfunction "1_1") (pintype "passive"))
    )
    (net (code "36") (name "Net-(D2-Pad3)") (class "Default")
      (node (ref "D2") (pin "3") (pinfunction "3_3") (pintype "passive"))
      (node (ref "R107") (pin "1") (pinfunction "1_1") (pintype "passive"))
    )
    (net (code "37") (name "Net-(D2-Pad4)") (class "Default")
      (node (ref "D2") (pin "4") (pinfunction "4_4") (pintype "passive"))
      (node (ref "R108") (pin "1") (pinfunction "1_1") (pintype "passive"))
    )
    (net (code "38") (name "Net-(GREEN-PadA)") (class "Default")
      (node (ref "GREEN") (pin "A") (pinfunction "A_A") (pintype "passive"))
      (node (ref "R8") (pin "2") (pinfunction "2_2") (pintype "passive"))
    )
    (net (code "39") (name "Net-(IND-PadA)") (class "Default")
      (node (ref "IND") (pin "A") (pinfunction "A_A") (pintype "passive"))
      (node (ref "R7") (pin "2") (pinfunction "2_2") (pintype "passive"))
    )
    (net (code "40") (name "Net-(J5-Pad1)") (class "Default")
      (node (ref "J5") (pin "1") (pinfunction "1_1") (pintype "bidirectional"))
      (node (ref "R9") (pin "2") (pinfunction "2_2") (pintype "passive"))
    )
    (net (code "41") (name "Net-(J5-Pad2)") (class "Default")
      (node (ref "J5") (pin "2") (pinfunction "2_2") (pintype "bidirectional"))
      (node (ref "R16") (pin "2") (pinfunction "2_2") (pintype "passive"))
    )
    (net (code "42") (name "Net-(J5-Pad3)") (class "Default")
      (node (ref "J5") (pin "3") (pinfunction "3_3") (pintype "bidirectional"))
      (node (ref "R14") (pin "2") (pinfunction "2_2") (pintype "passive"))
    )
    (net (code "43") (name "Net-(J5-Pad4)") (class "Default")
      (node (ref "J5") (pin "4") (pinfunction "4_4") (pintype "bidirectional"))
      (node (ref "R17") (pin "2") (pinfunction "2_2") (pintype "passive"))
    )
    (net (code "44") (name "Net-(J5-Pad6)") (class "Default")
      (node (ref "J5") (pin "6") (pinfunction "6_6") (pintype "bidirectional"))
      (node (ref "R18") (pin "2") (pinfunction "2_2") (pintype "passive"))
    )
    (net (code "45") (name "Net-(J5-Pad7)") (class "Default")
      (node (ref "J5") (pin "7") (pinfunction "7_7") (pintype "bidirectional"))
      (node (ref "R15") (pin "2") (pinfunction "2_2") (pintype "passive"))
    )
    (net (code "46") (name "Net-(J5-Pad8)") (class "Default")
      (node (ref "J5") (pin "8") (pinfunction "8_8") (pintype "bidirectional"))
      (node (ref "R19") (pin "2") (pinfunction "2_2") (pintype "passive"))
    )
    (net (code "47") (name "Net-(LOOP-PadA)") (class "Default")
      (node (ref "LOOP") (pin "A") (pinfunction "A_A") (pintype "passive"))
      (node (ref "R3") (pin "2") (pinfunction "2_2") (pintype "passive"))
    )
    (net (code "48") (name "Net-(Q1-2)") (class "Default")
      (node (ref "C31") (pin "1") (pinfunction "1_1") (pintype "passive"))
      (node (ref "Q1") (pin "3") (pinfunction "2_3") (pintype "passive"))
      (node (ref "STM32F446VET1") (pin "PH0") (pinfunction "PH0_PH0") (pintype "bidirectional"))
    )
    (net (code "49") (name "Net-(R5-Pad1)") (class "Default")
      (node (ref "R5") (pin "1") (pinfunction "1_1") (pintype "passive"))
      (node (ref "STM32F446VET1") (pin "PE8") (pinfunction "PE8_PE8") (pintype "bidirectional"))
    )
    (net (code "50") (name "Net-(R5-Pad2)") (class "Default")
      (node (ref "R5") (pin "2") (pinfunction "2_2") (pintype "passive"))
      (node (ref "RED") (pin "A") (pinfunction "A_A") (pintype "passive"))
    )
    (net (code "51") (name "Net-(R6-Pad1)") (class "Default")
      (node (ref "R6") (pin "1") (pinfunction "1_1") (pintype "passive"))
      (node (ref "STM32F446VET1") (pin "PE10") (pinfunction "PE10_PE10") (pintype "bidirectional"))
    )
    (net (code "52") (name "Net-(R8-Pad1)") (class "Default")
      (node (ref "R8") (pin "1") (pinfunction "1_1") (pintype "passive"))
      (node (ref "STM32F446VET1") (pin "PE9") (pinfunction "PE9_PE9") (pintype "bidirectional"))
    )
    (net (code "53") (name "Net-(R10-Pad2)") (class "Default")
      (node (ref "R10") (pin "2") (pinfunction "2_2") (pintype "passive"))
      (node (ref "STM32F446VET1") (pin "BOOT0") (pinfunction "BOOT0_BOOT0") (pintype "bidirectional"))
    )
    (net (code "54") (name "Net-(R25-Pad1)") (class "Default")
      (node (ref "R25") (pin "1") (pinfunction "1_1") (pintype "passive"))
      (node (ref "R26") (pin "1") (pinfunction "1_1") (pintype "passive"))
      (node (ref "T2") (pin "B") (pinfunction "B_B") (pintype "passive"))
    )
    (net (code "55") (name "Net-(R26-Pad2)") (class "Default")
      (node (ref "R26") (pin "2") (pinfunction "2_2") (pintype "passive"))
      (node (ref "T1") (pin "C") (pinfunction "C_C") (pintype "passive"))
    )
    (net (code "56") (name "Net-(R27-Pad1)") (class "Default")
      (node (ref "R27") (pin "1") (pinfunction "1_1") (pintype "passive"))
      (node (ref "T1") (pin "B") (pinfunction "B_B") (pintype "passive"))
    )
    (net (code "57") (name "Net-(STM32F446VET1-PB11)") (class "Default")
      (node (ref "STM32F446VET1") (pin "VCAP_1") (pinfunction "PB11_VCAP_1") (pintype "bidirectional"))
      (node (ref "VCAP4") (pin "1") (pinfunction "1_1") (pintype "passive"))
    )
    (net (code "58") (name "Net-(STM32F446VET1-VCAP_2)") (class "Default")
      (node (ref "STM32F446VET1") (pin "VCAP2") (pinfunction "VCAP_2_VCAP2") (pintype "bidirectional"))
      (node (ref "VCAP") (pin "1") (pinfunction "1_1") (pintype "passive"))
    )
    (net (code "59") (name "Net-(U$1-K)") (class "Default")
      (node (ref "D1") (pin "A") (pinfunction "A_A") (pintype "passive"))
      (node (ref "U$1") (pin "P$1") (pinfunction "K_P$1") (pintype "passive"))
    )
    (net (code "60") (name "Net-(U$2-SCK)") (class "Default")
      (node (ref "R126") (pin "1") (pinfunction "1_1") (pintype "passive"))
      (node (ref "U$2") (pin "16") (pinfunction "SCK_16") (pintype "bidirectional"))
    )
    (net (code "61") (name "Net-(U$2-SI)") (class "Default")
      (node (ref "R125") (pin "1") (pinfunction "1_1") (pintype "passive"))
      (node (ref "U$2") (pin "15") (pinfunction "SI_15") (pintype "bidirectional"))
    )
    (net (code "62") (name "Net-(U$2-SO)") (class "Default")
      (node (ref "R124") (pin "1") (pinfunction "1_1") (pintype "passive"))
      (node (ref "U$2") (pin "8") (pinfunction "SO_8") (pintype "bidirectional"))
    )
    (net (code "63") (name "Net-(U$2-~{CS})") (class "Default")
      (node (ref "R127") (pin "1") (pinfunction "1_1") (pintype "passive"))
      (node (ref "U$2") (pin "7") (pinfunction "~{CS}_7") (pintype "bidirectional"))
    )
    (net (code "64") (name "Net-(U$2-~{RESET})") (class "Default")
      (node (ref "R119") (pin "2") (pinfunction "2_2") (pintype "passive"))
      (node (ref "U$2") (pin "3") (pinfunction "~{RESET}_3") (pintype "bidirectional"))
    )
    (net (code "65") (name "Net-(U$4-CARD_DETECT)") (class "Default")
      (node (ref "R128") (pin "2") (pinfunction "2_2") (pintype "passive"))
      (node (ref "U$4") (pin "DETECT") (pinfunction "CARD_DETECT_DETECT") (pintype "passive"))
    )
    (net (code "66") (name "Net-(U$16-P$3)") (class "Default")
      (node (ref "R11") (pin "1") (pinfunction "1_1") (pintype "passive"))
      (node (ref "R12") (pin "2") (pinfunction "2_2") (pintype "passive"))
      (node (ref "R13") (pin "2") (pinfunction "2_2") (pintype "passive"))
      (node (ref "U$16") (pin "3") (pinfunction "P$3_3") (pintype "bidirectional"))
    )
    (net (code "67") (name "Net-(U11-REGOUT)") (class "Default")
      (node (ref "C51") (pin "1") (pinfunction "1_1") (pintype "passive"))
      (node (ref "U11") (pin "10") (pinfunction "REGOUT_10") (pintype "bidirectional"))
    )
    (net (code "68") (name "SD_CARD_CS") (class "Default")
      (node (ref "STM32F446VET1") (pin "PE4") (pinfunction "PE4_PE4") (pintype "bidirectional"))
      (node (ref "U$4") (pin "PIN2") (pinfunction "CS_PIN2") (pintype "input"))
    )
    (net (code "69") (name "SD_CARD_DETECT") (class "Default")
      (node (ref "C-FLASH1") (pin "2") (pinfunction "2_2") (pintype "passive"))
      (node (ref "R128") (pin "1") (pinfunction "1_1") (pintype "passive"))
      (node (ref "STM32F446VET1") (pin "PE3") (pinfunction "PE3_PE3") (pintype "bidirectional"))
    )
    (net (code "70") (name "SD_CARD_MISO") (class "Default")
      (node (ref "STM32F446VET1") (pin "PE5") (pinfunction "PE5_PE5") (pintype "bidirectional"))
      (node (ref "U$4") (pin "PIN7") (pinfunction "DATA_OUT_PIN7") (pintype "output"))
    )
    (net (code "71") (name "SD_CARD_MOSI") (class "Default")
      (node (ref "STM32F446VET1") (pin "PE6") (pinfunction "PE6_PE6") (pintype "bidirectional"))
      (node (ref "U$4") (pin "PIN3") (pinfunction "DATA_IN_PIN3") (pintype "input"))
    )
    (net (code "72") (name "SD_CARD_SCK") (class "Default")
      (node (ref "STM32F446VET1") (pin "PE2") (pinfunction "PE2_PE2") (pintype "bidirectional"))
      (node (ref "U$4") (pin "PIN5") (pinfunction "SCLK_PIN5") (pintype "input"))
    )
    (net (code "73") (name "SENSOR_AB_SCL") (class "Default")
      (node (ref "J6") (pin "3") (pinfunction "3_3") (pintype "bidirectional"))
      (node (ref "J8") (pin "3") (pinfunction "3_3") (pintype "bidirectional"))
      (node (ref "STM32F446VET1") (pin "PB10") (pinfunction "PB10_PB10") (pintype "bidirectional"))
    )
    (net (code "74") (name "SENSOR_A_DRDY") (class "Default")
      (node (ref "J8") (pin "5") (pinfunction "5_5") (pintype "bidirectional"))
      (node (ref "STM32F446VET1") (pin "PD14") (pinfunction "PD14_PD14") (pintype "bidirectional"))
    )
    (net (code "75") (name "SENSOR_A_PWM") (class "Default")
      (node (ref "J8") (pin "6") (pinfunction "6_6") (pintype "bidirectional"))
    )
    (net (code "76") (name "SENSOR_A_SDA") (class "Default")
      (node (ref "IC1") (pin "1") (pinfunction "A_1") (pintype "tri_state"))
      (node (ref "J8") (pin "4") (pinfunction "4_4") (pintype "bidirectional"))
    )
    (net (code "77") (name "SENSOR_B_DRDY") (class "Default")
      (node (ref "J6") (pin "5") (pinfunction "5_5") (pintype "bidirectional"))
      (node (ref "STM32F446VET1") (pin "PD13") (pinfunction "PD13_PD13") (pintype "bidirectional"))
    )
    (net (code "78") (name "SENSOR_B_PWM") (class "Default")
      (node (ref "J6") (pin "6") (pinfunction "6_6") (pintype "bidirectional"))
    )
    (net (code "79") (name "SENSOR_B_SDA") (class "Default")
      (node (ref "IC1") (pin "4") (pinfunction "A_4") (pintype "tri_state"))
      (node (ref "J6") (pin "4") (pinfunction "4_4") (pintype "bidirectional"))
    )
    (net (code "80") (name "SENSOR_C_DRDY") (class "Default")
      (node (ref "J7") (pin "5") (pinfunction "5_5") (pintype "bidirectional"))
      (node (ref "STM32F446VET1") (pin "PD12") (pinfunction "PD12_PD12") (pintype "bidirectional"))
    )
    (net (code "81") (name "SENSOR_C_PWM") (class "Default")
      (node (ref "J7") (pin "6") (pinfunction "6_6") (pintype "bidirectional"))
    )
    (net (code "82") (name "SENSOR_C_SCL") (class "Default")
      (node (ref "J7") (pin "3") (pinfunction "3_3") (pintype "bidirectional"))
      (node (ref "STM32F446VET1") (pin "PA8") (pinfunction "PA8_PA8") (pintype "bidirectional"))
    )
    (net (code "83") (name "SENSOR_C_SDA") (class "Default")
      (node (ref "J7") (pin "4") (pinfunction "4_4") (pintype "bidirectional"))
      (node (ref "STM32F446VET1") (pin "PC9") (pinfunction "PC9_PC9") (pintype "bidirectional"))
    )
    (net (code "84") (name "SENSOR_D_DRDY") (class "Default")
      (node (ref "J9") (pin "5") (pinfunction "5_5") (pintype "bidirectional"))
      (node (ref "STM32F446VET1") (pin "PD11") (pinfunction "PD11_PD11") (pintype "bidirectional"))
    )
    (net (code "85") (name "SENSOR_D_PWM") (class "Default")
      (node (ref "J9") (pin "6") (pinfunction "6_6") (pintype "bidirectional"))
    )
    (net (code "86") (name "SENSOR_D_SCL") (class "Default")
      (node (ref "J9") (pin "3") (pinfunction "3_3") (pintype "bidirectional"))
      (node (ref "STM32F446VET1") (pin "PB6") (pinfunction "PB6_PB6") (pintype "bidirectional"))
    )
    (net (code "87") (name "SENSOR_D_SDA") (class "Default")
      (node (ref "J9") (pin "4") (pinfunction "4_4") (pintype "bidirectional"))
      (node (ref "STM32F446VET1") (pin "PB7") (pinfunction "PB7_PB7") (pintype "bidirectional"))
    )
    (net (code "88") (name "STLINK_RX") (class "Default")
      (node (ref "STM32F446VET1") (pin "PD6") (pinfunction "PD6_PD6") (pintype "bidirectional"))
      (node (ref "U$5") (pin "8") (pinfunction "8_8") (pintype "passive"))
    )
    (net (code "89") (name "STLINK_TX") (class "Default")
      (node (ref "STM32F446VET1") (pin "PD5") (pinfunction "PD5_PD5") (pintype "bidirectional"))
      (node (ref "U$5") (pin "7") (pinfunction "7_7") (pintype "passive"))
    )
    (net (code "90") (name "SUPPLY") (class "Default")
      (node (ref "C1") (pin "1") (pinfunction "1_1") (pintype "passive"))
      (node (ref "C16") (pin "1") (pinfunction "1_1") (pintype "passive"))
      (node (ref "C17") (pin "1") (pinfunction "1_1") (pintype "passive"))
      (node (ref "C2") (pin "1") (pinfunction "1_1") (pintype "passive"))
      (node (ref "D1") (pin "C") (pinfunction "C_C") (pintype "passive"))
      (node (ref "R11") (pin "2") (pinfunction "2_2") (pintype "passive"))
      (node (ref "U1") (pin "1") (pinfunction "VIN_1") (pintype "input"))
      (node (ref "U3") (pin "1") (pinfunction "VIN_1") (pintype "input"))
    )
    (net (code "91") (name "SWCLK") (class "Default")
      (node (ref "STM32F446VET1") (pin "PA14") (pinfunction "PA14_PA14") (pintype "bidirectional"))
      (node (ref "U$5") (pin "3") (pinfunction "3_3") (pintype "passive"))
    )
    (net (code "92") (name "SWDIO") (class "Default")
      (node (ref "STM32F446VET1") (pin "PA13") (pinfunction "PA13_PA13") (pintype "bidirectional"))
      (node (ref "U$5") (pin "4") (pinfunction "4_4") (pintype "passive"))
    )
    (net (code "93") (name "SWO") (class "Default")
      (node (ref "U$5") (pin "2") (pinfunction "2_2") (pintype "passive"))
    )
    (net (code "94") (name "UVC_ADC_1") (class "Default")
      (node (ref "C20") (pin "1") (pinfunction "1_1") (pintype "passive"))
      (node (ref "R9") (pin "1") (pinfunction "1_1") (pintype "passive"))
      (node (ref "STM32F446VET1") (pin "PA3") (pinfunction "PA3_PA3") (pintype "bidirectional"))
    )
    (net (code "95") (name "UVC_ADC_2") (class "Default")
      (node (ref "C28") (pin "1") (pinfunction "1_1") (pintype "passive"))
      (node (ref "R16") (pin "1") (pinfunction "1_1") (pintype "passive"))
      (node (ref "STM32F446VET1") (pin "PC3") (pinfunction "PC3_PC3") (pintype "bidirectional"))
    )
    (net (code "96") (name "UVC_ADC_3") (class "Default")
      (node (ref "C25") (pin "1") (pinfunction "1_1") (pintype "passive"))
      (node (ref "R14") (pin "1") (pinfunction "1_1") (pintype "passive"))
      (node (ref "STM32F446VET1") (pin "PC2") (pinfunction "PC2_PC2") (pintype "bidirectional"))
    )
    (net (code "97") (name "UVC_ADC_4") (class "Default")
      (node (ref "C29") (pin "1") (pinfunction "1_1") (pintype "passive"))
      (node (ref "R17") (pin "1") (pinfunction "1_1") (pintype "passive"))
      (node (ref "STM32F446VET1") (pin "PC1") (pinfunction "PC1_PC1") (pintype "bidirectional"))
    )
    (net (code "98") (name "UVC_ADC_5") (class "Default")
      (node (ref "C30") (pin "1") (pinfunction "1_1") (pintype "passive"))
      (node (ref "R18") (pin "1") (pinfunction "1_1") (pintype "passive"))
      (node (ref "STM32F446VET1") (pin "PC0") (pinfunction "PC0_PC0") (pintype "bidirectional"))
    )
    (net (code "99") (name "UVC_ADC_6") (class "Default")
      (node (ref "C27") (pin "1") (pinfunction "1_1") (pintype "passive"))
      (node (ref "R15") (pin "1") (pinfunction "1_1") (pintype "passive"))
      (node (ref "STM32F446VET1") (pin "PB1") (pinfunction "PB1_PB1") (pintype "bidirectional"))
    )
    (net (code "100") (name "UVC_ADC_7") (class "Default")
      (node (ref "C33") (pin "1") (pinfunction "1_1") (pintype "passive"))
      (node (ref "R19") (pin "1") (pinfunction "1_1") (pintype "passive"))
      (node (ref "STM32F446VET1") (pin "PB0") (pinfunction "PB0_PB0") (pintype "bidirectional"))
    )
    (net (code "101") (name "UVC_BOARD_SUPPLY") (class "Default")
      (node (ref "C18") (pin "1") (pinfunction "1_1") (pintype "passive"))
      (node (ref "C19") (pin "1") (pinfunction "1_1") (pintype "passive"))
      (node (ref "J5") (pin "10") (pinfunction "10_10") (pintype "bidirectional"))
      (node (ref "R25") (pin "2") (pinfunction "2_2") (pintype "passive"))
      (node (ref "R4") (pin "1") (pinfunction "1_1") (pintype "passive"))
      (node (ref "T2") (pin "E") (pinfunction "E_E") (pintype "passive"))
      (node (ref "U3") (pin "3") (pinfunction "VOUT_3") (pintype "output"))
    )
    (net (code "102") (name "VBAT") (class "Default")
      (node (ref "C48") (pin "1") (pinfunction "1_1") (pintype "passive"))
      (node (ref "STM32F446VET1") (pin "VBAT") (pinfunction "VBAT_VBAT") (pintype "bidirectional"))
      (node (ref "U$32") (pin "+") (pinfunction "+_+") (pintype "bidirectional"))
    )
    (net (code "103") (name "unconnected-(IC1C-A-Pad8)") (class "Default")
      (node (ref "IC1") (pin "8") (pinfunction "A_8") (pintype "tri_state"))
    )
    (net (code "104") (name "unconnected-(IC1C-B-Pad9)") (class "Default")
      (node (ref "IC1") (pin "9") (pinfunction "B_9") (pintype "tri_state"))
    )
    (net (code "105") (name "unconnected-(IC1C-C-Pad6)") (class "Default")
      (node (ref "IC1") (pin "6") (pinfunction "C_6") (pintype "input"))
    )
    (net (code "106") (name "unconnected-(IC1D-A-Pad11)") (class "Default")
      (node (ref "IC1") (pin "11") (pinfunction "A_11") (pintype "tri_state"))
    )
    (net (code "107") (name "unconnected-(IC1D-B-Pad10)") (class "Default")
      (node (ref "IC1") (pin "10") (pinfunction "B_10") (pintype "tri_state"))
    )
    (net (code "108") (name "unconnected-(IC1D-C-Pad12)") (class "Default")
      (node (ref "IC1") (pin "12") (pinfunction "C_12") (pintype "input"))
    )
    (net (code "109") (name "unconnected-(STM32F446VET1-PadPA9)") (class "Default")
      (node (ref "STM32F446VET1") (pin "PA9") (pinfunction "PA9_PA9") (pintype "bidirectional"))
    )
    (net (code "110") (name "unconnected-(STM32F446VET1-PadPA10)") (class "Default")
      (node (ref "STM32F446VET1") (pin "PA10") (pinfunction "PA10_PA10") (pintype "bidirectional"))
    )
    (net (code "111") (name "unconnected-(STM32F446VET1-PadPA11)") (class "Default")
      (node (ref "STM32F446VET1") (pin "PA11") (pinfunction "PA11_PA11") (pintype "bidirectional"))
    )
    (net (code "112") (name "unconnected-(STM32F446VET1-PadPA12)") (class "Default")
      (node (ref "STM32F446VET1") (pin "PA12") (pinfunction "PA12_PA12") (pintype "bidirectional"))
    )
    (net (code "113") (name "unconnected-(STM32F446VET1-PadPB2)") (class "Default")
      (node (ref "STM32F446VET1") (pin "PB2") (pinfunction "PB2_PB2") (pintype "bidirectional"))
    )
    (net (code "114") (name "unconnected-(STM32F446VET1-PadPB8)") (class "Default")
      (node (ref "STM32F446VET1") (pin "PB8") (pinfunction "PB8_PB8") (pintype "bidirectional"))
    )
    (net (code "115") (name "unconnected-(STM32F446VET1-PadPB9)") (class "Default")
      (node (ref "STM32F446VET1") (pin "PB9") (pinfunction "PB9_PB9") (pintype "bidirectional"))
    )
    (net (code "116") (name "unconnected-(STM32F446VET1-PadPC6)") (class "Default")
      (node (ref "STM32F446VET1") (pin "PC6") (pinfunction "PC6_PC6") (pintype "bidirectional"))
    )
    (net (code "117") (name "unconnected-(STM32F446VET1-PadPC7)") (class "Default")
      (node (ref "STM32F446VET1") (pin "PC7") (pinfunction "PC7_PC7") (pintype "bidirectional"))
    )
    (net (code "118") (name "unconnected-(STM32F446VET1-PadPC8)") (class "Default")
      (node (ref "STM32F446VET1") (pin "PC8") (pinfunction "PC8_PC8") (pintype "bidirectional"))
    )
    (net (code "119") (name "unconnected-(STM32F446VET1-PadPC10)") (class "Default")
      (node (ref "STM32F446VET1") (pin "PC10") (pinfunction "PC10_PC10") (pintype "bidirectional"))
    )
    (net (code "120") (name "unconnected-(STM32F446VET1-PadPC11)") (class "Default")
      (node (ref "STM32F446VET1") (pin "PC11") (pinfunction "PC11_PC11") (pintype "bidirectional"))
    )
    (net (code "121") (name "unconnected-(STM32F446VET1-PadPC13)") (class "Default")
      (node (ref "STM32F446VET1") (pin "PC13") (pinfunction "PC13_PC13") (pintype "bidirectional"))
    )
    (net (code "122") (name "unconnected-(STM32F446VET1-PadPD0)") (class "Default")
      (node (ref "STM32F446VET1") (pin "PD0") (pinfunction "PD0_PD0") (pintype "bidirectional"))
    )
    (net (code "123") (name "unconnected-(STM32F446VET1-PadPD1)") (class "Default")
      (node (ref "STM32F446VET1") (pin "PD1") (pinfunction "PD1_PD1") (pintype "bidirectional"))
    )
    (net (code "124") (name "unconnected-(STM32F446VET1-PadPD2)") (class "Default")
      (node (ref "STM32F446VET1") (pin "PD2") (pinfunction "PD2_PD2") (pintype "bidirectional"))
    )
    (net (code "125") (name "unconnected-(STM32F446VET1-PadPD3)") (class "Default")
      (node (ref "STM32F446VET1") (pin "PD3") (pinfunction "PD3_PD3") (pintype "bidirectional"))
    )
    (net (code "126") (name "unconnected-(STM32F446VET1-PadPD4)") (class "Default")
      (node (ref "STM32F446VET1") (pin "PD4") (pinfunction "PD4_PD4") (pintype "bidirectional"))
    )
    (net (code "127") (name "unconnected-(STM32F446VET1-PadPD9)") (class "Default")
      (node (ref "STM32F446VET1") (pin "PD9") (pinfunction "PD9_PD9") (pintype "bidirectional"))
    )
    (net (code "128") (name "unconnected-(STM32F446VET1-PadPD10)") (class "Default")
      (node (ref "STM32F446VET1") (pin "PD10") (pinfunction "PD10_PD10") (pintype "bidirectional"))
    )
    (net (code "129") (name "unconnected-(STM32F446VET1-PadPD15)") (class "Default")
      (node (ref "STM32F446VET1") (pin "PD15") (pinfunction "PD15_PD15") (pintype "bidirectional"))
    )
    (net (code "130") (name "unconnected-(STM32F446VET1-PadPE7)") (class "Default")
      (node (ref "STM32F446VET1") (pin "PE7") (pinfunction "PE7_PE7") (pintype "bidirectional"))
    )
    (net (code "131") (name "unconnected-(STM32F446VET1-PadPE11)") (class "Default")
      (node (ref "STM32F446VET1") (pin "PE11") (pinfunction "PE11_PE11") (pintype "bidirectional"))
    )
    (net (code "132") (name "unconnected-(STM32F446VET1-PadPE12)") (class "Default")
      (node (ref "STM32F446VET1") (pin "PE12") (pinfunction "PE12_PE12") (pintype "bidirectional"))
    )
    (net (code "133") (name "unconnected-(STM32F446VET1-PadPE15)") (class "Default")
      (node (ref "STM32F446VET1") (pin "PE15") (pinfunction "PE15_PE15") (pintype "bidirectional"))
    )
    (net (code "134") (name "unconnected-(U$2-IO3{slash}~{RESET}-Pad1)") (class "Default")
      (node (ref "U$2") (pin "1") (pinfunction "IO3/~{RESET}_1") (pintype "bidirectional"))
    )
    (net (code "135") (name "unconnected-(U$2-~{WP}-Pad9)") (class "Default")
      (node (ref "U$2") (pin "9") (pinfunction "~{WP}_9") (pintype "bidirectional"))
    )
    (net (code "136") (name "unconnected-(U$4-DAT1-PadPIN8)") (class "Default")
      (node (ref "U$4") (pin "PIN8") (pinfunction "DAT1_PIN8") (pintype "bidirectional"))
    )
    (net (code "137") (name "unconnected-(U$4-DAT2-PadPIN1)") (class "Default")
      (node (ref "U$4") (pin "PIN1") (pinfunction "DAT2_PIN1") (pintype "bidirectional"))
    )
    (net (code "138") (name "unconnected-(U11-AUX_CL-Pad7)") (class "Default")
      (node (ref "U11") (pin "7") (pinfunction "AUX_CL_7") (pintype "bidirectional"))
    )
    (net (code "139") (name "unconnected-(U11-AUX_DA-Pad21)") (class "Default")
      (node (ref "U11") (pin "21") (pinfunction "AUX_DA_21") (pintype "bidirectional"))
    )
    (net (code "140") (name "unconnected-(U11-FSYNC-Pad11)") (class "Default")
      (node (ref "U11") (pin "11") (pinfunction "FSYNC_11") (pintype "bidirectional"))
    )
    (net (code "141") (name "unconnected-(U11-NC-Pad2)") (class "Default")
      (node (ref "U11") (pin "2") (pinfunction "NC_2") (pintype "bidirectional"))
    )
    (net (code "142") (name "unconnected-(U11-NC-Pad3)") (class "Default")
      (node (ref "U11") (pin "3") (pinfunction "NC_3") (pintype "bidirectional"))
    )
    (net (code "143") (name "unconnected-(U11-NC-Pad4)") (class "Default")
      (node (ref "U11") (pin "4") (pinfunction "NC_4") (pintype "bidirectional"))
    )
    (net (code "144") (name "unconnected-(U11-NC-Pad5)") (class "Default")
      (node (ref "U11") (pin "5") (pinfunction "NC_5") (pintype "bidirectional"))
    )
    (net (code "145") (name "unconnected-(U11-NC-Pad6)") (class "Default")
      (node (ref "U11") (pin "6") (pinfunction "NC_6") (pintype "bidirectional"))
    )
    (net (code "146") (name "unconnected-(U11-NC-Pad14)") (class "Default")
      (node (ref "U11") (pin "14") (pinfunction "NC_14") (pintype "bidirectional"))
    )
    (net (code "147") (name "unconnected-(U11-NC-Pad15)") (class "Default")
      (node (ref "U11") (pin "15") (pinfunction "NC_15") (pintype "bidirectional"))
    )
    (net (code "148") (name "unconnected-(U11-NC-Pad16)") (class "Default")
      (node (ref "U11") (pin "16") (pinfunction "NC_16") (pintype "bidirectional"))
    )
    (net (code "149") (name "unconnected-(U11-NC-Pad17)") (class "Default")
      (node (ref "U11") (pin "17") (pinfunction "NC_17") (pintype "bidirectional"))
    )
    (net (code "150") (name "unconnected-(U11-RESV-Pad19)") (class "Default")
      (node (ref "U11") (pin "19") (pinfunction "RESV_19") (pintype "bidirectional"))
    )
  )
)
